# 2015Xover.net
KiCad netlist of a schematic drawn in EAGLE
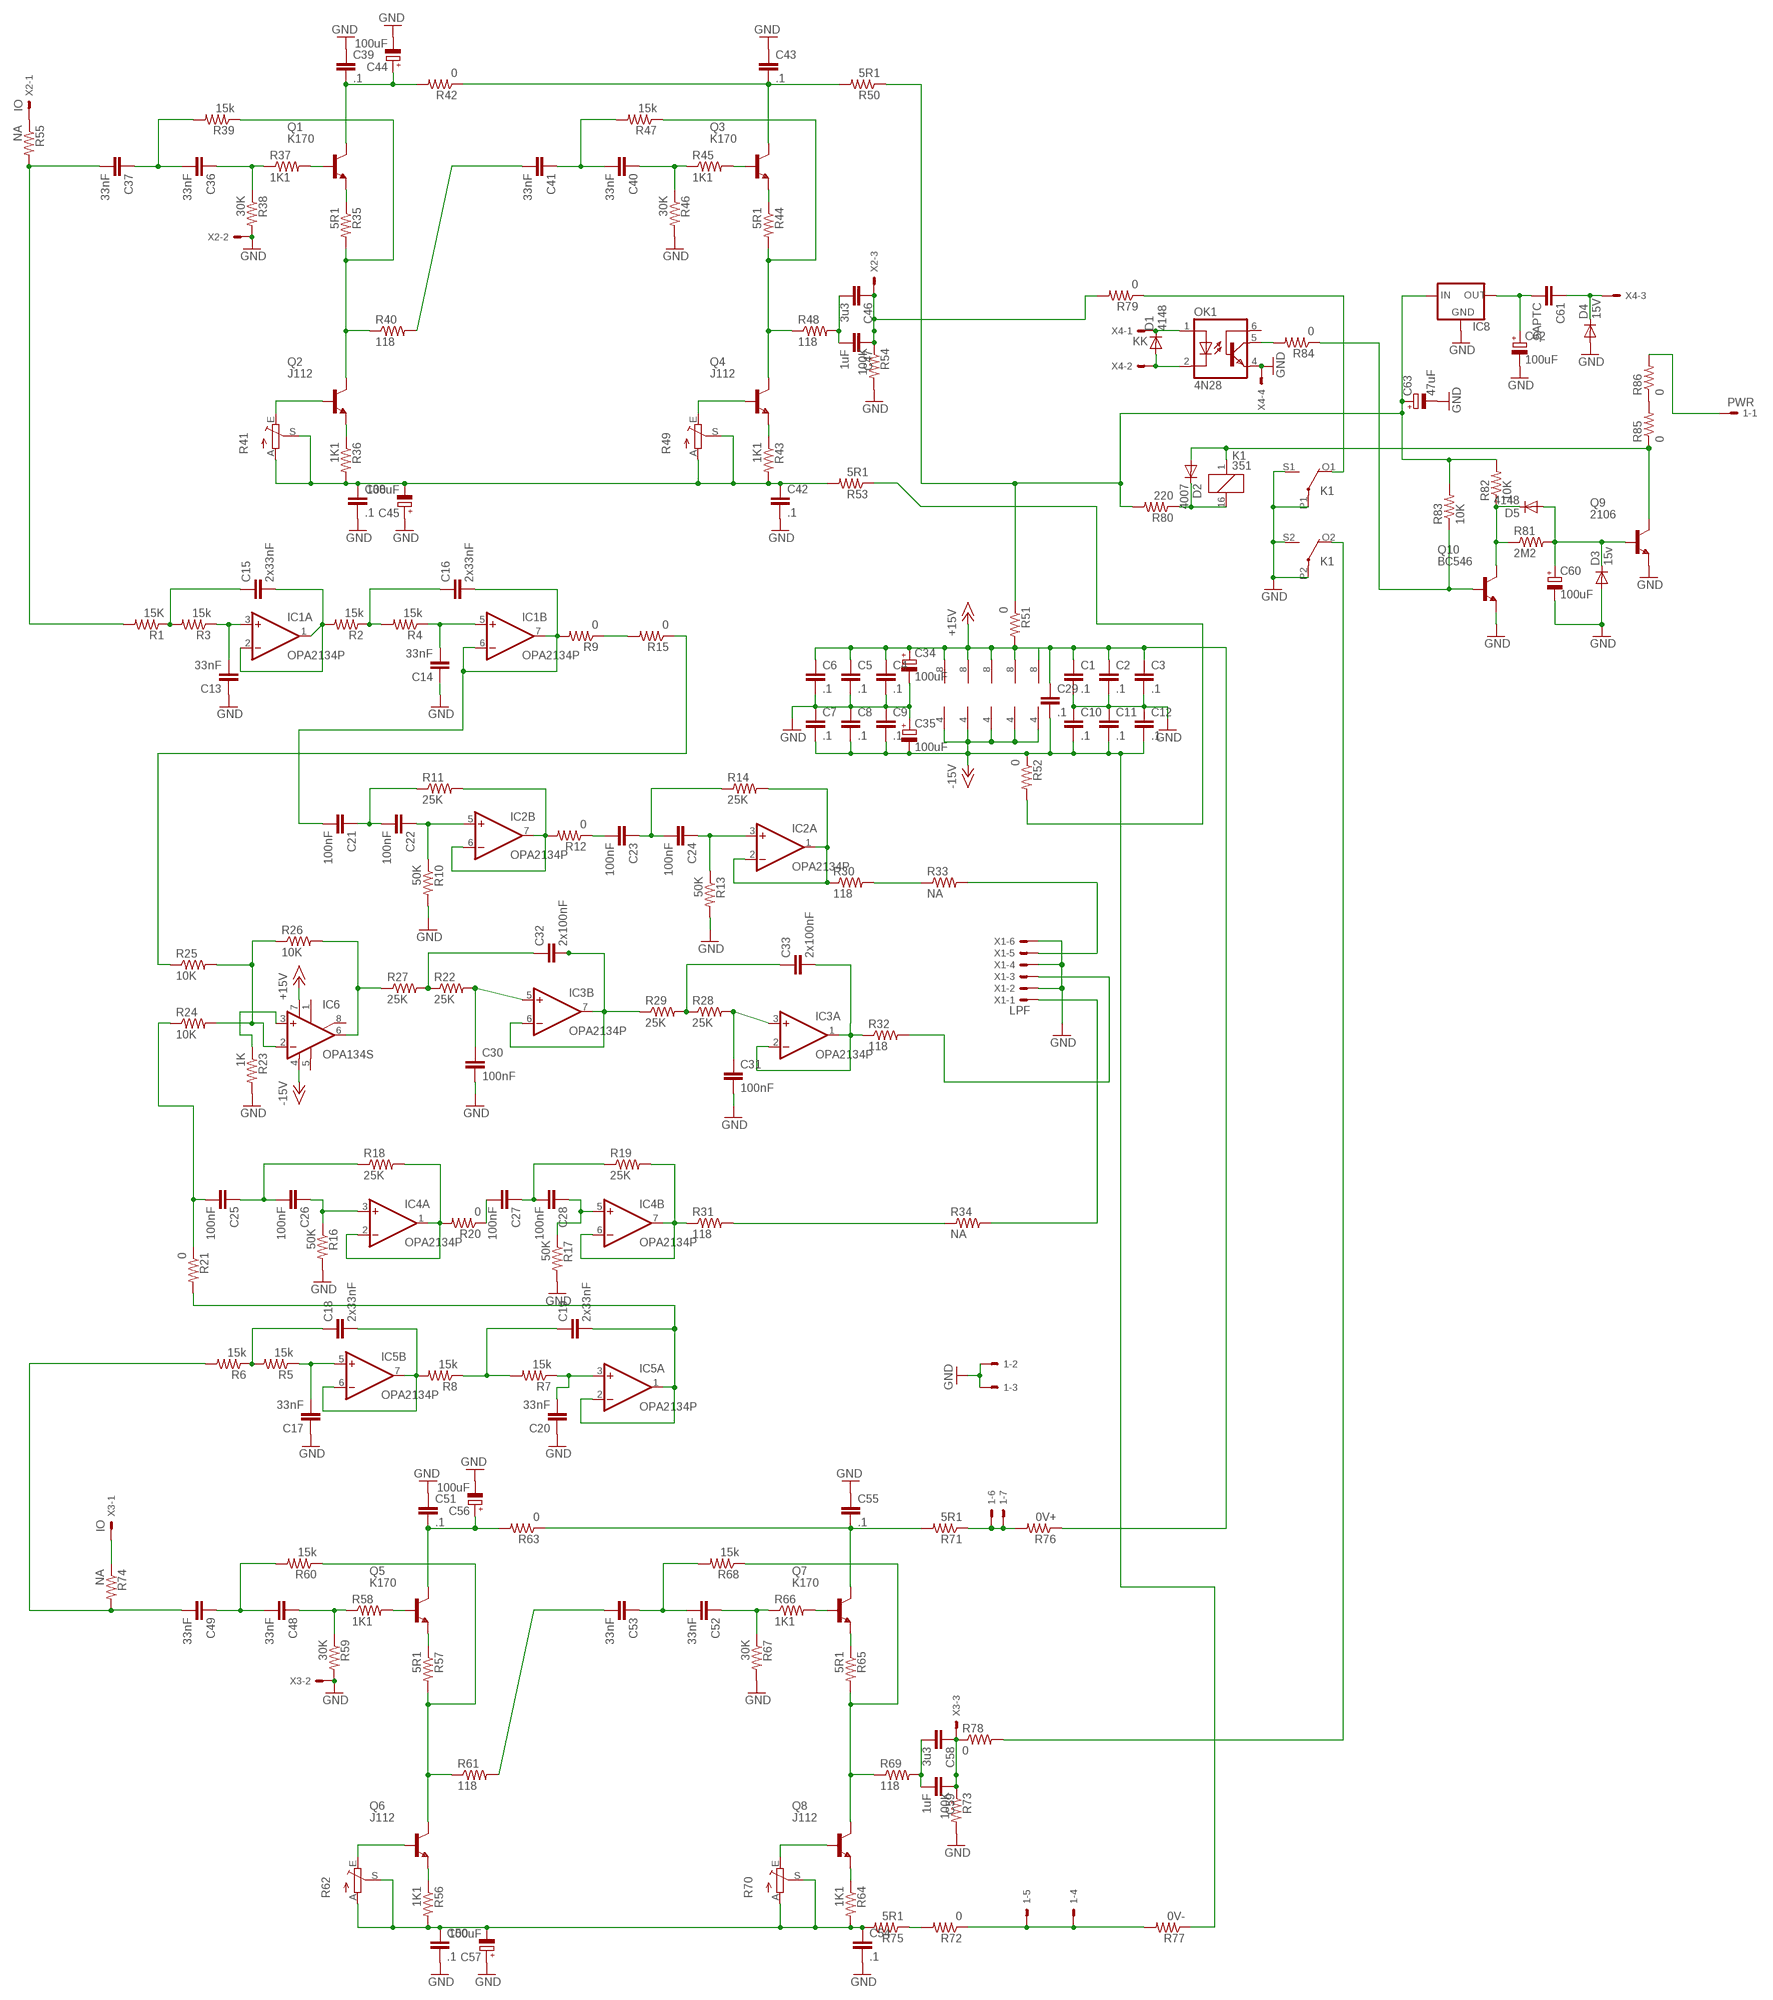
[diagram p0: schematic, sheet 1]

(export (version "E")
  (design (tool "Eeschema 10.0.6"))
  (components
    (comp (ref "1")
      (value "PWR")
      (footprint "eagle-import:22-23-2071")
      (fields (field (name "MF") "MOLEX") (field (name "MPN") "22-23-2071"))
      (libsource (lib "eagle-import") (part "22-23-2071"))
    )
    (comp (ref "C1")
      (value ".1")
      (footprint "eagle-import:C4532")
      (libsource (lib "eagle-import") (part "C-EUC4532"))
    )
    (comp (ref "C2")
      (value ".1")
      (footprint "eagle-import:C4532")
      (libsource (lib "eagle-import") (part "C-EUC4532"))
    )
    (comp (ref "C3")
      (value ".1")
      (footprint "eagle-import:C4532")
      (libsource (lib "eagle-import") (part "C-EUC4532"))
    )
    (comp (ref "C4")
      (value ".1")
      (footprint "eagle-import:C4532")
      (libsource (lib "eagle-import") (part "C-EUC4532"))
    )
    (comp (ref "C5")
      (value ".1")
      (footprint "eagle-import:C4532")
      (libsource (lib "eagle-import") (part "C-EUC4532"))
    )
    (comp (ref "C6")
      (value ".1")
      (footprint "eagle-import:C4532")
      (libsource (lib "eagle-import") (part "C-EUC4532"))
    )
    (comp (ref "C7")
      (value ".1")
      (footprint "eagle-import:C4532")
      (libsource (lib "eagle-import") (part "C-EUC4532"))
    )
    (comp (ref "C8")
      (value ".1")
      (footprint "eagle-import:C4532")
      (libsource (lib "eagle-import") (part "C-EUC4532"))
    )
    (comp (ref "C9")
      (value ".1")
      (footprint "eagle-import:C4532")
      (libsource (lib "eagle-import") (part "C-EUC4532"))
    )
    (comp (ref "C10")
      (value ".1")
      (footprint "eagle-import:C4532")
      (libsource (lib "eagle-import") (part "C-EUC4532"))
    )
    (comp (ref "C11")
      (value ".1")
      (footprint "eagle-import:C4532")
      (libsource (lib "eagle-import") (part "C-EUC4532"))
    )
    (comp (ref "C12")
      (value ".1")
      (footprint "eagle-import:C4532")
      (libsource (lib "eagle-import") (part "C-EUC4532"))
    )
    (comp (ref "C13")
      (value "33nF")
      (footprint "eagle-import:C050-075X075")
      (libsource (lib "eagle-import") (part "C-EU050-075X075"))
    )
    (comp (ref "C14")
      (value "33nF")
      (footprint "eagle-import:C050-075X075")
      (libsource (lib "eagle-import") (part "C-EU050-075X075"))
    )
    (comp (ref "C15")
      (value "2x33nF")
      (footprint "eagle-import:C050-075X075")
      (libsource (lib "eagle-import") (part "C-EU050-075X075"))
    )
    (comp (ref "C16")
      (value "2x33nF")
      (footprint "eagle-import:C050-075X075")
      (libsource (lib "eagle-import") (part "C-EU050-075X075"))
    )
    (comp (ref "C17")
      (value "33nF")
      (footprint "eagle-import:C050-075X075")
      (libsource (lib "eagle-import") (part "C-EU050-075X075"))
    )
    (comp (ref "C18")
      (value "2x33nF")
      (footprint "eagle-import:C050-075X075")
      (libsource (lib "eagle-import") (part "C-EU050-075X075"))
    )
    (comp (ref "C19")
      (value "2x33nF")
      (footprint "eagle-import:C050-075X075")
      (libsource (lib "eagle-import") (part "C-EU050-075X075"))
    )
    (comp (ref "C20")
      (value "33nF")
      (footprint "eagle-import:C050-075X075")
      (libsource (lib "eagle-import") (part "C-EU050-075X075"))
    )
    (comp (ref "C21")
      (value "100nF")
      (footprint "eagle-import:C050-075X075")
      (libsource (lib "eagle-import") (part "C-EU050-075X075"))
    )
    (comp (ref "C22")
      (value "100nF")
      (footprint "eagle-import:C050-075X075")
      (libsource (lib "eagle-import") (part "C-EU050-075X075"))
    )
    (comp (ref "C23")
      (value "100nF")
      (footprint "eagle-import:C050-075X075")
      (libsource (lib "eagle-import") (part "C-EU050-075X075"))
    )
    (comp (ref "C24")
      (value "100nF")
      (footprint "eagle-import:C050-075X075")
      (libsource (lib "eagle-import") (part "C-EU050-075X075"))
    )
    (comp (ref "C25")
      (value "100nF")
      (footprint "eagle-import:C050-075X075")
      (libsource (lib "eagle-import") (part "C-EU050-075X075"))
    )
    (comp (ref "C26")
      (value "100nF")
      (footprint "eagle-import:C050-075X075")
      (libsource (lib "eagle-import") (part "C-EU050-075X075"))
    )
    (comp (ref "C27")
      (value "100nF")
      (footprint "eagle-import:C050-075X075")
      (libsource (lib "eagle-import") (part "C-EU050-075X075"))
    )
    (comp (ref "C28")
      (value "100nF")
      (footprint "eagle-import:C050-075X075")
      (libsource (lib "eagle-import") (part "C-EU050-075X075"))
    )
    (comp (ref "C29")
      (value ".1")
      (footprint "eagle-import:C4532")
      (libsource (lib "eagle-import") (part "C-EUC4532"))
    )
    (comp (ref "C30")
      (value "100nF")
      (footprint "eagle-import:C050-075X075")
      (libsource (lib "eagle-import") (part "C-EU050-075X075"))
    )
    (comp (ref "C31")
      (value "100nF")
      (footprint "eagle-import:C050-075X075")
      (libsource (lib "eagle-import") (part "C-EU050-075X075"))
    )
    (comp (ref "C32")
      (value "2x100nF")
      (footprint "eagle-import:C050-075X075")
      (libsource (lib "eagle-import") (part "C-EU050-075X075"))
    )
    (comp (ref "C33")
      (value "2x100nF")
      (footprint "eagle-import:C050-075X075")
      (libsource (lib "eagle-import") (part "C-EU050-075X075"))
    )
    (comp (ref "C34")
      (value "100uF")
      (footprint "eagle-import:E5-10,5")
      (libsource (lib "eagle-import") (part "CPOL-EUE5-10.5"))
    )
    (comp (ref "C35")
      (value "100uF")
      (footprint "eagle-import:E5-10,5")
      (libsource (lib "eagle-import") (part "CPOL-EUE5-10.5"))
    )
    (comp (ref "C36")
      (value "33nF")
      (footprint "eagle-import:C050-075X075")
      (libsource (lib "eagle-import") (part "C-EU050-075X075"))
    )
    (comp (ref "C37")
      (value "33nF")
      (footprint "eagle-import:C050-075X075")
      (libsource (lib "eagle-import") (part "C-EU050-075X075"))
    )
    (comp (ref "C38")
      (value ".1")
      (footprint "eagle-import:C4532")
      (libsource (lib "eagle-import") (part "C-EUC4532"))
    )
    (comp (ref "C39")
      (value ".1")
      (footprint "eagle-import:C4532")
      (libsource (lib "eagle-import") (part "C-EUC4532"))
    )
    (comp (ref "C40")
      (value "33nF")
      (footprint "eagle-import:C050-075X075")
      (libsource (lib "eagle-import") (part "C-EU050-075X075"))
    )
    (comp (ref "C41")
      (value "33nF")
      (footprint "eagle-import:C050-075X075")
      (libsource (lib "eagle-import") (part "C-EU050-075X075"))
    )
    (comp (ref "C42")
      (value ".1")
      (footprint "eagle-import:C4532")
      (libsource (lib "eagle-import") (part "C-EUC4532"))
    )
    (comp (ref "C43")
      (value ".1")
      (footprint "eagle-import:C4532")
      (libsource (lib "eagle-import") (part "C-EUC4532"))
    )
    (comp (ref "C44")
      (value "100uF")
      (footprint "eagle-import:E5-10,5")
      (libsource (lib "eagle-import") (part "CPOL-EUE5-10.5"))
    )
    (comp (ref "C45")
      (value "100uF")
      (footprint "eagle-import:E5-10,5")
      (libsource (lib "eagle-import") (part "CPOL-EUE5-10.5"))
    )
    (comp (ref "C46")
      (value "3u3")
      (footprint "eagle-import:C275-134X316")
      (libsource (lib "eagle-import") (part "C-EU275-134X316"))
    )
    (comp (ref "C47")
      (value "1uF")
      (footprint "eagle-import:C275-134X316")
      (libsource (lib "eagle-import") (part "C-EU275-134X316"))
    )
    (comp (ref "C48")
      (value "33nF")
      (footprint "eagle-import:C050-075X075")
      (libsource (lib "eagle-import") (part "C-EU050-075X075"))
    )
    (comp (ref "C49")
      (value "33nF")
      (footprint "eagle-import:C050-075X075")
      (libsource (lib "eagle-import") (part "C-EU050-075X075"))
    )
    (comp (ref "C50")
      (value ".1")
      (footprint "eagle-import:C4532")
      (libsource (lib "eagle-import") (part "C-EUC4532"))
    )
    (comp (ref "C51")
      (value ".1")
      (footprint "eagle-import:C4532")
      (libsource (lib "eagle-import") (part "C-EUC4532"))
    )
    (comp (ref "C52")
      (value "33nF")
      (footprint "eagle-import:C050-075X075")
      (libsource (lib "eagle-import") (part "C-EU050-075X075"))
    )
    (comp (ref "C53")
      (value "33nF")
      (footprint "eagle-import:C050-075X075")
      (libsource (lib "eagle-import") (part "C-EU050-075X075"))
    )
    (comp (ref "C54")
      (value ".1")
      (footprint "eagle-import:C4532")
      (libsource (lib "eagle-import") (part "C-EUC4532"))
    )
    (comp (ref "C55")
      (value ".1")
      (footprint "eagle-import:C4532")
      (libsource (lib "eagle-import") (part "C-EUC4532"))
    )
    (comp (ref "C56")
      (value "100uF")
      (footprint "eagle-import:E5-10,5")
      (libsource (lib "eagle-import") (part "CPOL-EUE5-10.5"))
    )
    (comp (ref "C57")
      (value "100uF")
      (footprint "eagle-import:E5-10,5")
      (libsource (lib "eagle-import") (part "CPOL-EUE5-10.5"))
    )
    (comp (ref "C58")
      (value "3u3")
      (footprint "eagle-import:C275-134X316")
      (libsource (lib "eagle-import") (part "C-EU275-134X316"))
    )
    (comp (ref "C59")
      (value "1uF")
      (footprint "eagle-import:C275-134X316")
      (libsource (lib "eagle-import") (part "C-EU275-134X316"))
    )
    (comp (ref "C60")
      (value "100uF")
      (footprint "eagle-import:E5-10,5")
      (libsource (lib "eagle-import") (part "CPOL-EUE5-10.5"))
    )
    (comp (ref "C61")
      (value ".5APTC")
      (footprint "eagle-import:C050-075X075")
      (libsource (lib "eagle-import") (part "C-EU050-075X075"))
    )
    (comp (ref "C62")
      (value "100uF")
      (footprint "eagle-import:E5-10,5")
      (libsource (lib "eagle-import") (part "CPOL-EUE5-10.5"))
    )
    (comp (ref "C63")
      (value "47uF")
      (footprint "eagle-import:E5-10,5")
      (libsource (lib "eagle-import") (part "CPOL-EUE5-10.5"))
    )
    (comp (ref "D1")
      (value "4148")
      (footprint "eagle-import:DO35-7")
      (libsource (lib "eagle-import") (part "1N4148DO35-7"))
    )
    (comp (ref "D2")
      (value "4007")
      (footprint "eagle-import:DO35-7")
      (libsource (lib "eagle-import") (part "1N4148DO35-7"))
    )
    (comp (ref "D3")
      (value "15v")
      (footprint "eagle-import:DO35-7")
      (libsource (lib "eagle-import") (part "1N4148DO35-7"))
    )
    (comp (ref "D4")
      (value "15V")
      (footprint "eagle-import:DO35-7")
      (libsource (lib "eagle-import") (part "1N4148DO35-7"))
    )
    (comp (ref "D5")
      (value "4148")
      (footprint "eagle-import:DO35-7")
      (libsource (lib "eagle-import") (part "1N4148DO35-7"))
    )
    (comp (ref "IC1")
      (value "OPA2134P")
      (footprint "eagle-import:DIL08")
      (libsource (lib "eagle-import") (part "OPA2134P"))
    )
    (comp (ref "IC2")
      (value "OPA2134P")
      (footprint "eagle-import:DIL08")
      (libsource (lib "eagle-import") (part "OPA2134P"))
    )
    (comp (ref "IC3")
      (value "OPA2134P")
      (footprint "eagle-import:DIL08")
      (libsource (lib "eagle-import") (part "OPA2134P"))
    )
    (comp (ref "IC4")
      (value "OPA2134P")
      (footprint "eagle-import:DIL08")
      (libsource (lib "eagle-import") (part "OPA2134P"))
    )
    (comp (ref "IC5")
      (value "OPA2134P")
      (footprint "eagle-import:DIL08")
      (libsource (lib "eagle-import") (part "OPA2134P"))
    )
    (comp (ref "IC6")
      (value "OPA134S")
      (footprint "eagle-import:DIL08")
      (libsource (lib "eagle-import") (part "OPA134P"))
    )
    (comp (ref "IC8")
      (value "78XXS")
      (footprint "eagle-import:78XXS")
      (libsource (lib "eagle-import") (part "78XXS"))
    )
    (comp (ref "K1")
      (value "351")
      (footprint "eagle-import:351")
      (libsource (lib "eagle-import") (part "351"))
    )
    (comp (ref "OK1")
      (value "4N28")
      (footprint "eagle-import:DIL06")
      (fields (field (name "MF") "FAIRCHILD SEMICONDUCTOR") (field (name "MPN") "4N35"))
      (libsource (lib "eagle-import") (part "4N35"))
    )
    (comp (ref "Q1")
      (value "K170")
      (footprint "eagle-import:TO92-EBC")
      (libsource (lib "eagle-import") (part "BC546A"))
    )
    (comp (ref "Q2")
      (value "J112")
      (footprint "eagle-import:TO92-EBC")
      (libsource (lib "eagle-import") (part "BC546A"))
    )
    (comp (ref "Q3")
      (value "K170")
      (footprint "eagle-import:TO92-EBC")
      (libsource (lib "eagle-import") (part "BC546A"))
    )
    (comp (ref "Q4")
      (value "J112")
      (footprint "eagle-import:TO92-EBC")
      (libsource (lib "eagle-import") (part "BC546A"))
    )
    (comp (ref "Q5")
      (value "K170")
      (footprint "eagle-import:TO92-EBC")
      (libsource (lib "eagle-import") (part "BC546A"))
    )
    (comp (ref "Q6")
      (value "J112")
      (footprint "eagle-import:TO92-EBC")
      (libsource (lib "eagle-import") (part "BC546A"))
    )
    (comp (ref "Q7")
      (value "K170")
      (footprint "eagle-import:TO92-EBC")
      (libsource (lib "eagle-import") (part "BC546A"))
    )
    (comp (ref "Q8")
      (value "J112")
      (footprint "eagle-import:TO92-EBC")
      (libsource (lib "eagle-import") (part "BC546A"))
    )
    (comp (ref "Q9")
      (value "2106")
      (footprint "eagle-import:TO92-EBC")
      (libsource (lib "eagle-import") (part "BC546A"))
    )
    (comp (ref "Q10")
      (value "BC546")
      (footprint "eagle-import:TO92-EBC")
      (libsource (lib "eagle-import") (part "BC546A"))
    )
    (comp (ref "R1")
      (value "15K")
      (footprint "eagle-import:0309_10")
      (libsource (lib "eagle-import") (part "R-US_0309/10"))
    )
    (comp (ref "R2")
      (value "15k")
      (footprint "eagle-import:0309_12")
      (libsource (lib "eagle-import") (part "R-US_0309/12"))
    )
    (comp (ref "R3")
      (value "15k")
      (footprint "eagle-import:0309_10")
      (libsource (lib "eagle-import") (part "R-US_0309/10"))
    )
    (comp (ref "R4")
      (value "15k")
      (footprint "eagle-import:0309_12")
      (libsource (lib "eagle-import") (part "R-US_0309/12"))
    )
    (comp (ref "R5")
      (value "15k")
      (footprint "eagle-import:0309_10")
      (libsource (lib "eagle-import") (part "R-US_0309/10"))
    )
    (comp (ref "R6")
      (value "15k")
      (footprint "eagle-import:0309_10")
      (libsource (lib "eagle-import") (part "R-US_0309/10"))
    )
    (comp (ref "R7")
      (value "15k")
      (footprint "eagle-import:0309_10")
      (libsource (lib "eagle-import") (part "R-US_0309/10"))
    )
    (comp (ref "R8")
      (value "15k")
      (footprint "eagle-import:0309_12")
      (libsource (lib "eagle-import") (part "R-US_0309/12"))
    )
    (comp (ref "R9")
      (value "0")
      (footprint "eagle-import:0309_12")
      (libsource (lib "eagle-import") (part "R-US_0309/12"))
    )
    (comp (ref "R10")
      (value "50K")
      (footprint "eagle-import:0309_10")
      (libsource (lib "eagle-import") (part "R-US_0309/10"))
    )
    (comp (ref "R11")
      (value "25K")
      (footprint "eagle-import:0309_10")
      (libsource (lib "eagle-import") (part "R-US_0309/10"))
    )
    (comp (ref "R12")
      (value "0")
      (footprint "eagle-import:0309_12")
      (libsource (lib "eagle-import") (part "R-US_0309/12"))
    )
    (comp (ref "R13")
      (value "50K")
      (footprint "eagle-import:0309_12")
      (libsource (lib "eagle-import") (part "R-US_0309/12"))
    )
    (comp (ref "R14")
      (value "25K")
      (footprint "eagle-import:0309_10")
      (libsource (lib "eagle-import") (part "R-US_0309/10"))
    )
    (comp (ref "R15")
      (value "0")
      (footprint "eagle-import:0309_12")
      (libsource (lib "eagle-import") (part "R-US_0309/12"))
    )
    (comp (ref "R16")
      (value "50K")
      (footprint "eagle-import:0309_12")
      (libsource (lib "eagle-import") (part "R-US_0309/12"))
    )
    (comp (ref "R17")
      (value "50K")
      (footprint "eagle-import:0309_10")
      (libsource (lib "eagle-import") (part "R-US_0309/10"))
    )
    (comp (ref "R18")
      (value "25K")
      (footprint "eagle-import:0309_10")
      (libsource (lib "eagle-import") (part "R-US_0309/10"))
    )
    (comp (ref "R19")
      (value "25K")
      (footprint "eagle-import:0309_10")
      (libsource (lib "eagle-import") (part "R-US_0309/10"))
    )
    (comp (ref "R20")
      (value "0")
      (footprint "eagle-import:0309_12")
      (libsource (lib "eagle-import") (part "R-US_0309/12"))
    )
    (comp (ref "R21")
      (value "0")
      (footprint "eagle-import:0309_10")
      (libsource (lib "eagle-import") (part "R-US_0309/10"))
    )
    (comp (ref "R22")
      (value "25K")
      (footprint "eagle-import:0309_10")
      (libsource (lib "eagle-import") (part "R-US_0309/10"))
    )
    (comp (ref "R23")
      (value "1K")
      (footprint "eagle-import:0309_10")
      (libsource (lib "eagle-import") (part "R-US_0309/10"))
    )
    (comp (ref "R24")
      (value "10K")
      (footprint "eagle-import:0309_10")
      (libsource (lib "eagle-import") (part "R-US_0309/10"))
    )
    (comp (ref "R25")
      (value "10K")
      (footprint "eagle-import:0309_12")
      (libsource (lib "eagle-import") (part "R-US_0309/12"))
    )
    (comp (ref "R26")
      (value "10K")
      (footprint "eagle-import:0309_12")
      (libsource (lib "eagle-import") (part "R-US_0309/12"))
    )
    (comp (ref "R27")
      (value "25K")
      (footprint "eagle-import:0309_10")
      (libsource (lib "eagle-import") (part "R-US_0309/10"))
    )
    (comp (ref "R28")
      (value "25K")
      (footprint "eagle-import:0309_10")
      (libsource (lib "eagle-import") (part "R-US_0309/10"))
    )
    (comp (ref "R29")
      (value "25K")
      (footprint "eagle-import:0309_12")
      (libsource (lib "eagle-import") (part "R-US_0309/12"))
    )
    (comp (ref "R30")
      (value "118")
      (footprint "eagle-import:0309_10")
      (libsource (lib "eagle-import") (part "R-US_0309/10"))
    )
    (comp (ref "R31")
      (value "118")
      (footprint "eagle-import:0309_12")
      (libsource (lib "eagle-import") (part "R-US_0309/12"))
    )
    (comp (ref "R32")
      (value "118")
      (footprint "eagle-import:0309_10")
      (libsource (lib "eagle-import") (part "R-US_0309/10"))
    )
    (comp (ref "R33")
      (value "NA")
      (footprint "eagle-import:0309_10")
      (libsource (lib "eagle-import") (part "R-US_0309/10"))
    )
    (comp (ref "R34")
      (value "NA")
      (footprint "eagle-import:0309_10")
      (libsource (lib "eagle-import") (part "R-US_0309/10"))
    )
    (comp (ref "R35")
      (value "5R1")
      (footprint "eagle-import:0309_10")
      (libsource (lib "eagle-import") (part "R-US_0309/10"))
    )
    (comp (ref "R36")
      (value "1K1")
      (footprint "eagle-import:R1210")
      (libsource (lib "eagle-import") (part "R-US_R1210"))
    )
    (comp (ref "R37")
      (value "1K1")
      (footprint "eagle-import:R1210")
      (libsource (lib "eagle-import") (part "R-US_R1210"))
    )
    (comp (ref "R38")
      (value "30K")
      (footprint "eagle-import:0309_10")
      (libsource (lib "eagle-import") (part "R-US_0309/10"))
    )
    (comp (ref "R39")
      (value "15k")
      (footprint "eagle-import:0309_10")
      (libsource (lib "eagle-import") (part "R-US_0309/10"))
    )
    (comp (ref "R40")
      (value "118")
      (footprint "eagle-import:0309_10")
      (libsource (lib "eagle-import") (part "R-US_0309/10"))
    )
    (comp (ref "R41")
      (value "TRIM_EU-RJ9W")
      (footprint "eagle-import:RJ9W")
      (libsource (lib "eagle-import") (part "TRIM_EU-RJ9W"))
    )
    (comp (ref "R42")
      (value "0")
      (footprint "eagle-import:0309_10")
      (libsource (lib "eagle-import") (part "R-US_0309/10"))
    )
    (comp (ref "R43")
      (value "1K1")
      (footprint "eagle-import:R1210")
      (libsource (lib "eagle-import") (part "R-US_R1210"))
    )
    (comp (ref "R44")
      (value "5R1")
      (footprint "eagle-import:0309_10")
      (libsource (lib "eagle-import") (part "R-US_0309/10"))
    )
    (comp (ref "R45")
      (value "1K1")
      (footprint "eagle-import:R1210")
      (libsource (lib "eagle-import") (part "R-US_R1210"))
    )
    (comp (ref "R46")
      (value "30K")
      (footprint "eagle-import:0309_10")
      (libsource (lib "eagle-import") (part "R-US_0309/10"))
    )
    (comp (ref "R47")
      (value "15k")
      (footprint "eagle-import:0309_10")
      (libsource (lib "eagle-import") (part "R-US_0309/10"))
    )
    (comp (ref "R48")
      (value "118")
      (footprint "eagle-import:0309_10")
      (libsource (lib "eagle-import") (part "R-US_0309/10"))
    )
    (comp (ref "R49")
      (value "TRIM_EU-RJ9W")
      (footprint "eagle-import:RJ9W")
      (libsource (lib "eagle-import") (part "TRIM_EU-RJ9W"))
    )
    (comp (ref "R50")
      (value "5R1")
      (footprint "eagle-import:0309_10")
      (libsource (lib "eagle-import") (part "R-US_0309/10"))
    )
    (comp (ref "R51")
      (value "0")
      (footprint "eagle-import:0309_10")
      (libsource (lib "eagle-import") (part "R-US_0309/10"))
    )
    (comp (ref "R52")
      (value "0")
      (footprint "eagle-import:0309_10")
      (libsource (lib "eagle-import") (part "R-US_0309/10"))
    )
    (comp (ref "R53")
      (value "5R1")
      (footprint "eagle-import:0309_10")
      (libsource (lib "eagle-import") (part "R-US_0309/10"))
    )
    (comp (ref "R54")
      (value "100K")
      (footprint "eagle-import:0309_10")
      (libsource (lib "eagle-import") (part "R-US_0309/10"))
    )
    (comp (ref "R55")
      (value "NA")
      (footprint "eagle-import:0309_12")
      (libsource (lib "eagle-import") (part "R-US_0309/12"))
    )
    (comp (ref "R56")
      (value "1K1")
      (footprint "eagle-import:R1210")
      (libsource (lib "eagle-import") (part "R-US_R1210"))
    )
    (comp (ref "R57")
      (value "5R1")
      (footprint "eagle-import:0309_10")
      (libsource (lib "eagle-import") (part "R-US_0309/10"))
    )
    (comp (ref "R58")
      (value "1K1")
      (footprint "eagle-import:R1210")
      (libsource (lib "eagle-import") (part "R-US_R1210"))
    )
    (comp (ref "R59")
      (value "30K")
      (footprint "eagle-import:0309_10")
      (libsource (lib "eagle-import") (part "R-US_0309/10"))
    )
    (comp (ref "R60")
      (value "15k")
      (footprint "eagle-import:0309_10")
      (libsource (lib "eagle-import") (part "R-US_0309/10"))
    )
    (comp (ref "R61")
      (value "118")
      (footprint "eagle-import:0309_10")
      (libsource (lib "eagle-import") (part "R-US_0309/10"))
    )
    (comp (ref "R62")
      (value "TRIM_EU-RJ9W")
      (footprint "eagle-import:RJ9W")
      (libsource (lib "eagle-import") (part "TRIM_EU-RJ9W"))
    )
    (comp (ref "R63")
      (value "0")
      (footprint "eagle-import:0309_10")
      (libsource (lib "eagle-import") (part "R-US_0309/10"))
    )
    (comp (ref "R64")
      (value "1K1")
      (footprint "eagle-import:R1210")
      (libsource (lib "eagle-import") (part "R-US_R1210"))
    )
    (comp (ref "R65")
      (value "5R1")
      (footprint "eagle-import:0309_10")
      (libsource (lib "eagle-import") (part "R-US_0309/10"))
    )
    (comp (ref "R66")
      (value "1K1")
      (footprint "eagle-import:R1210")
      (libsource (lib "eagle-import") (part "R-US_R1210"))
    )
    (comp (ref "R67")
      (value "30K")
      (footprint "eagle-import:0309_10")
      (libsource (lib "eagle-import") (part "R-US_0309/10"))
    )
    (comp (ref "R68")
      (value "15k")
      (footprint "eagle-import:0309_10")
      (libsource (lib "eagle-import") (part "R-US_0309/10"))
    )
    (comp (ref "R69")
      (value "118")
      (footprint "eagle-import:0309_10")
      (libsource (lib "eagle-import") (part "R-US_0309/10"))
    )
    (comp (ref "R70")
      (value "TRIM_EU-RJ9W")
      (footprint "eagle-import:RJ9W")
      (libsource (lib "eagle-import") (part "TRIM_EU-RJ9W"))
    )
    (comp (ref "R71")
      (value "5R1")
      (footprint "eagle-import:0309_10")
      (libsource (lib "eagle-import") (part "R-US_0309/10"))
    )
    (comp (ref "R72")
      (value "0")
      (footprint "eagle-import:0309_12")
      (libsource (lib "eagle-import") (part "R-US_0309/12"))
    )
    (comp (ref "R73")
      (value "100K")
      (footprint "eagle-import:0309_10")
      (libsource (lib "eagle-import") (part "R-US_0309/10"))
    )
    (comp (ref "R74")
      (value "NA")
      (footprint "eagle-import:0309_12")
      (libsource (lib "eagle-import") (part "R-US_0309/12"))
    )
    (comp (ref "R75")
      (value "5R1")
      (footprint "eagle-import:0309_10")
      (libsource (lib "eagle-import") (part "R-US_0309/10"))
    )
    (comp (ref "R76")
      (value "0V+")
      (footprint "eagle-import:0309_10")
      (libsource (lib "eagle-import") (part "R-US_0309/10"))
    )
    (comp (ref "R77")
      (value "0V-")
      (footprint "eagle-import:0309_12")
      (libsource (lib "eagle-import") (part "R-US_0309/12"))
    )
    (comp (ref "R78")
      (value "0")
      (footprint "eagle-import:0309_12")
      (libsource (lib "eagle-import") (part "R-US_0309/12"))
    )
    (comp (ref "R79")
      (value "0")
      (footprint "eagle-import:0309_10")
      (libsource (lib "eagle-import") (part "R-US_0309/10"))
    )
    (comp (ref "R80")
      (value "220")
      (footprint "eagle-import:0309_10")
      (libsource (lib "eagle-import") (part "R-US_0309/10"))
    )
    (comp (ref "R81")
      (value "2M2")
      (footprint "eagle-import:0207_10")
      (libsource (lib "eagle-import") (part "R-US_0207/10"))
    )
    (comp (ref "R82")
      (value "10K")
      (footprint "eagle-import:0207_10")
      (libsource (lib "eagle-import") (part "R-US_0207/10"))
    )
    (comp (ref "R83")
      (value "10K")
      (footprint "eagle-import:0207_10")
      (libsource (lib "eagle-import") (part "R-US_0207/10"))
    )
    (comp (ref "R84")
      (value "0")
      (footprint "eagle-import:0309_10")
      (libsource (lib "eagle-import") (part "R-US_0309/10"))
    )
    (comp (ref "R85")
      (value "0")
      (footprint "eagle-import:0207_12")
      (libsource (lib "eagle-import") (part "R-US_0207/12"))
    )
    (comp (ref "R86")
      (value "0")
      (footprint "eagle-import:0207_10")
      (libsource (lib "eagle-import") (part "R-US_0207/10"))
    )
    (comp (ref "X1")
      (value "LPF")
      (footprint "eagle-import:22-23-2061")
      (fields (field (name "MF") "MOLEX") (field (name "MPN") "22-23-2061"))
      (libsource (lib "eagle-import") (part "22-23-2061"))
    )
    (comp (ref "X2")
      (value "IO")
      (footprint "eagle-import:22-23-2031")
      (fields (field (name "MF") "MOLEX") (field (name "MPN") "22-23-2031"))
      (libsource (lib "eagle-import") (part "22-23-2031"))
    )
    (comp (ref "X3")
      (value "IO")
      (footprint "eagle-import:22-23-2031")
      (fields (field (name "MF") "MOLEX") (field (name "MPN") "22-23-2031"))
      (libsource (lib "eagle-import") (part "22-23-2031"))
    )
    (comp (ref "X4")
      (value "KK")
      (footprint "eagle-import:22-23-2041")
      (fields (field (name "MF") "MOLEX") (field (name "MPN") "22-23-2041"))
      (libsource (lib "eagle-import") (part "22-23-2041"))
    )
  )
  (nets
    (net (code "1") (name "+15V") (class "Default")
      (node (ref "C1") (pin "1") (pinfunction "1_1") (pintype "passive"))
      (node (ref "C2") (pin "1") (pinfunction "1_1") (pintype "passive"))
      (node (ref "C29") (pin "1") (pinfunction "1_1") (pintype "passive"))
      (node (ref "C3") (pin "1") (pinfunction "1_1") (pintype "passive"))
      (node (ref "C34") (pin "+") (pinfunction "+_+") (pintype "passive"))
      (node (ref "C4") (pin "1") (pinfunction "1_1") (pintype "passive"))
      (node (ref "C5") (pin "1") (pinfunction "1_1") (pintype "passive"))
      (node (ref "C6") (pin "1") (pinfunction "1_1") (pintype "passive"))
      (node (ref "IC1") (pin "8") (pinfunction "V+_8") (pintype "power_in"))
      (node (ref "IC2") (pin "8") (pinfunction "V+_8") (pintype "power_in"))
      (node (ref "IC3") (pin "8") (pinfunction "V+_8") (pintype "power_in"))
      (node (ref "IC4") (pin "8") (pinfunction "V+_8") (pintype "power_in"))
      (node (ref "IC5") (pin "8") (pinfunction "V+_8") (pintype "power_in"))
      (node (ref "IC6") (pin "7") (pinfunction "V+_7") (pintype "power_in"))
      (node (ref "R51") (pin "2") (pinfunction "2_2") (pintype "passive"))
      (node (ref "R76") (pin "1") (pinfunction "1_1") (pintype "passive"))
    )
    (net (code "2") (name "-15V") (class "Default")
      (node (ref "C10") (pin "2") (pinfunction "2_2") (pintype "passive"))
      (node (ref "C11") (pin "2") (pinfunction "2_2") (pintype "passive"))
      (node (ref "C12") (pin "2") (pinfunction "2_2") (pintype "passive"))
      (node (ref "C29") (pin "2") (pinfunction "2_2") (pintype "passive"))
      (node (ref "C35") (pin "-") (pinfunction "-_-") (pintype "passive"))
      (node (ref "C7") (pin "2") (pinfunction "2_2") (pintype "passive"))
      (node (ref "C8") (pin "2") (pinfunction "2_2") (pintype "passive"))
      (node (ref "C9") (pin "2") (pinfunction "2_2") (pintype "passive"))
      (node (ref "IC1") (pin "4") (pinfunction "V-_4") (pintype "power_in"))
      (node (ref "IC2") (pin "4") (pinfunction "V-_4") (pintype "power_in"))
      (node (ref "IC3") (pin "4") (pinfunction "V-_4") (pintype "power_in"))
      (node (ref "IC4") (pin "4") (pinfunction "V-_4") (pintype "power_in"))
      (node (ref "IC5") (pin "4") (pinfunction "V-_4") (pintype "power_in"))
      (node (ref "IC6") (pin "4") (pinfunction "V-_4") (pintype "power_in"))
      (node (ref "R52") (pin "1") (pinfunction "1_1") (pintype "passive"))
      (node (ref "R77") (pin "1") (pinfunction "1_1") (pintype "passive"))
    )
    (net (code "3") (name "GND") (class "Default")
      (node (ref "1") (pin "2") (pinfunction "S_2") (pintype "passive"))
      (node (ref "1") (pin "3") (pinfunction "S_3") (pintype "passive"))
      (node (ref "C1") (pin "2") (pinfunction "2_2") (pintype "passive"))
      (node (ref "C10") (pin "1") (pinfunction "1_1") (pintype "passive"))
      (node (ref "C11") (pin "1") (pinfunction "1_1") (pintype "passive"))
      (node (ref "C12") (pin "1") (pinfunction "1_1") (pintype "passive"))
      (node (ref "C13") (pin "1") (pinfunction "1_1") (pintype "passive"))
      (node (ref "C14") (pin "1") (pinfunction "1_1") (pintype "passive"))
      (node (ref "C17") (pin "1") (pinfunction "1_1") (pintype "passive"))
      (node (ref "C2") (pin "2") (pinfunction "2_2") (pintype "passive"))
      (node (ref "C20") (pin "1") (pinfunction "1_1") (pintype "passive"))
      (node (ref "C3") (pin "2") (pinfunction "2_2") (pintype "passive"))
      (node (ref "C30") (pin "2") (pinfunction "2_2") (pintype "passive"))
      (node (ref "C31") (pin "2") (pinfunction "2_2") (pintype "passive"))
      (node (ref "C34") (pin "-") (pinfunction "-_-") (pintype "passive"))
      (node (ref "C35") (pin "+") (pinfunction "+_+") (pintype "passive"))
      (node (ref "C38") (pin "2") (pinfunction "2_2") (pintype "passive"))
      (node (ref "C39") (pin "1") (pinfunction "1_1") (pintype "passive"))
      (node (ref "C4") (pin "2") (pinfunction "2_2") (pintype "passive"))
      (node (ref "C42") (pin "2") (pinfunction "2_2") (pintype "passive"))
      (node (ref "C43") (pin "1") (pinfunction "1_1") (pintype "passive"))
      (node (ref "C44") (pin "-") (pinfunction "-_-") (pintype "passive"))
      (node (ref "C45") (pin "+") (pinfunction "+_+") (pintype "passive"))
      (node (ref "C5") (pin "2") (pinfunction "2_2") (pintype "passive"))
      (node (ref "C50") (pin "2") (pinfunction "2_2") (pintype "passive"))
      (node (ref "C51") (pin "1") (pinfunction "1_1") (pintype "passive"))
      (node (ref "C54") (pin "2") (pinfunction "2_2") (pintype "passive"))
      (node (ref "C55") (pin "1") (pinfunction "1_1") (pintype "passive"))
      (node (ref "C56") (pin "-") (pinfunction "-_-") (pintype "passive"))
      (node (ref "C57") (pin "+") (pinfunction "+_+") (pintype "passive"))
      (node (ref "C6") (pin "2") (pinfunction "2_2") (pintype "passive"))
      (node (ref "C60") (pin "-") (pinfunction "-_-") (pintype "passive"))
      (node (ref "C62") (pin "-") (pinfunction "-_-") (pintype "passive"))
      (node (ref "C63") (pin "-") (pinfunction "-_-") (pintype "passive"))
      (node (ref "C7") (pin "1") (pinfunction "1_1") (pintype "passive"))
      (node (ref "C8") (pin "1") (pinfunction "1_1") (pintype "passive"))
      (node (ref "C9") (pin "1") (pinfunction "1_1") (pintype "passive"))
      (node (ref "D3") (pin "A") (pinfunction "A_A") (pintype "passive"))
      (node (ref "D4") (pin "A") (pinfunction "A_A") (pintype "passive"))
      (node (ref "IC8") (pin "GND") (pinfunction "GND_GND") (pintype "input"))
      (node (ref "K1") (pin "P1") (pinfunction "P_P1") (pintype "passive"))
      (node (ref "K1") (pin "P2") (pinfunction "P_P2") (pintype "passive"))
      (node (ref "K1") (pin "S1") (pinfunction "S_S1") (pintype "passive"))
      (node (ref "K1") (pin "S2") (pinfunction "S_S2") (pintype "passive"))
      (node (ref "OK1") (pin "4") (pinfunction "EMI_4") (pintype "passive"))
      (node (ref "Q10") (pin "E") (pinfunction "E_E") (pintype "passive"))
      (node (ref "Q9") (pin "E") (pinfunction "E_E") (pintype "passive"))
      (node (ref "R10") (pin "2") (pinfunction "2_2") (pintype "passive"))
      (node (ref "R13") (pin "2") (pinfunction "2_2") (pintype "passive"))
      (node (ref "R16") (pin "2") (pinfunction "2_2") (pintype "passive"))
      (node (ref "R17") (pin "2") (pinfunction "2_2") (pintype "passive"))
      (node (ref "R23") (pin "2") (pinfunction "2_2") (pintype "passive"))
      (node (ref "R38") (pin "2") (pinfunction "2_2") (pintype "passive"))
      (node (ref "R46") (pin "2") (pinfunction "2_2") (pintype "passive"))
      (node (ref "R54") (pin "2") (pinfunction "2_2") (pintype "passive"))
      (node (ref "R59") (pin "2") (pinfunction "2_2") (pintype "passive"))
      (node (ref "R67") (pin "2") (pinfunction "2_2") (pintype "passive"))
      (node (ref "R73") (pin "2") (pinfunction "2_2") (pintype "passive"))
      (node (ref "X1") (pin "2") (pinfunction "S_2") (pintype "passive"))
      (node (ref "X1") (pin "4") (pinfunction "S_4") (pintype "passive"))
      (node (ref "X1") (pin "6") (pinfunction "S_6") (pintype "passive"))
      (node (ref "X2") (pin "2") (pinfunction "S_2") (pintype "passive"))
      (node (ref "X3") (pin "2") (pinfunction "S_2") (pintype "passive"))
      (node (ref "X4") (pin "4") (pinfunction "S_4") (pintype "passive"))
    )
    (net (code "4") (name "Net-(1A-S)") (class "Default")
      (node (ref "1") (pin "1") (pinfunction "S_1") (pintype "passive"))
      (node (ref "R86") (pin "2") (pinfunction "2_2") (pintype "passive"))
    )
    (net (code "5") (name "Net-(1D-S)") (class "Default")
      (node (ref "1") (pin "4") (pinfunction "S_4") (pintype "passive"))
      (node (ref "1") (pin "5") (pinfunction "S_5") (pintype "passive"))
      (node (ref "R72") (pin "1") (pinfunction "1_1") (pintype "passive"))
      (node (ref "R77") (pin "2") (pinfunction "2_2") (pintype "passive"))
    )
    (net (code "6") (name "Net-(1F-S)") (class "Default")
      (node (ref "1") (pin "6") (pinfunction "S_6") (pintype "passive"))
      (node (ref "1") (pin "7") (pinfunction "S_7") (pintype "passive"))
      (node (ref "R71") (pin "1") (pinfunction "1_1") (pintype "passive"))
      (node (ref "R76") (pin "2") (pinfunction "2_2") (pintype "passive"))
    )
    (net (code "7") (name "Net-(C15-Pad1)") (class "Default")
      (node (ref "C15") (pin "1") (pinfunction "1_1") (pintype "passive"))
      (node (ref "R1") (pin "1") (pinfunction "1_1") (pintype "passive"))
      (node (ref "R3") (pin "2") (pinfunction "2_2") (pintype "passive"))
    )
    (net (code "8") (name "Net-(C16-Pad1)") (class "Default")
      (node (ref "C16") (pin "1") (pinfunction "1_1") (pintype "passive"))
      (node (ref "R2") (pin "1") (pinfunction "1_1") (pintype "passive"))
      (node (ref "R4") (pin "2") (pinfunction "2_2") (pintype "passive"))
    )
    (net (code "9") (name "Net-(C18-Pad1)") (class "Default")
      (node (ref "C18") (pin "1") (pinfunction "1_1") (pintype "passive"))
      (node (ref "R5") (pin "2") (pinfunction "2_2") (pintype "passive"))
      (node (ref "R6") (pin "1") (pinfunction "1_1") (pintype "passive"))
    )
    (net (code "10") (name "Net-(C19-Pad1)") (class "Default")
      (node (ref "C19") (pin "1") (pinfunction "1_1") (pintype "passive"))
      (node (ref "R7") (pin "2") (pinfunction "2_2") (pintype "passive"))
      (node (ref "R8") (pin "1") (pinfunction "1_1") (pintype "passive"))
    )
    (net (code "11") (name "Net-(C21-Pad1)") (class "Default")
      (node (ref "C21") (pin "1") (pinfunction "1_1") (pintype "passive"))
      (node (ref "C22") (pin "2") (pinfunction "2_2") (pintype "passive"))
      (node (ref "R11") (pin "1") (pinfunction "1_1") (pintype "passive"))
    )
    (net (code "12") (name "Net-(C23-Pad1)") (class "Default")
      (node (ref "C23") (pin "1") (pinfunction "1_1") (pintype "passive"))
      (node (ref "C24") (pin "2") (pinfunction "2_2") (pintype "passive"))
      (node (ref "R14") (pin "1") (pinfunction "1_1") (pintype "passive"))
    )
    (net (code "13") (name "Net-(C23-Pad2)") (class "Default")
      (node (ref "C23") (pin "2") (pinfunction "2_2") (pintype "passive"))
      (node (ref "R12") (pin "1") (pinfunction "1_1") (pintype "passive"))
    )
    (net (code "14") (name "Net-(C25-Pad1)") (class "Default")
      (node (ref "C25") (pin "1") (pinfunction "1_1") (pintype "passive"))
      (node (ref "C26") (pin "2") (pinfunction "2_2") (pintype "passive"))
      (node (ref "R18") (pin "1") (pinfunction "1_1") (pintype "passive"))
    )
    (net (code "15") (name "Net-(C25-Pad2)") (class "Default")
      (node (ref "C25") (pin "2") (pinfunction "2_2") (pintype "passive"))
      (node (ref "R21") (pin "1") (pinfunction "1_1") (pintype "passive"))
      (node (ref "R24") (pin "1") (pinfunction "1_1") (pintype "passive"))
    )
    (net (code "16") (name "Net-(C27-Pad1)") (class "Default")
      (node (ref "C27") (pin "1") (pinfunction "1_1") (pintype "passive"))
      (node (ref "C28") (pin "2") (pinfunction "2_2") (pintype "passive"))
      (node (ref "R19") (pin "1") (pinfunction "1_1") (pintype "passive"))
    )
    (net (code "17") (name "Net-(C27-Pad2)") (class "Default")
      (node (ref "C27") (pin "2") (pinfunction "2_2") (pintype "passive"))
      (node (ref "R20") (pin "1") (pinfunction "1_1") (pintype "passive"))
    )
    (net (code "18") (name "Net-(C32-Pad1)") (class "Default")
      (node (ref "C32") (pin "1") (pinfunction "1_1") (pintype "passive"))
      (node (ref "R22") (pin "1") (pinfunction "1_1") (pintype "passive"))
      (node (ref "R27") (pin "2") (pinfunction "2_2") (pintype "passive"))
    )
    (net (code "19") (name "Net-(C33-Pad1)") (class "Default")
      (node (ref "C33") (pin "1") (pinfunction "1_1") (pintype "passive"))
      (node (ref "R28") (pin "1") (pinfunction "1_1") (pintype "passive"))
      (node (ref "R29") (pin "2") (pinfunction "2_2") (pintype "passive"))
    )
    (net (code "20") (name "Net-(C36-Pad1)") (class "Default")
      (node (ref "C36") (pin "1") (pinfunction "1_1") (pintype "passive"))
      (node (ref "R37") (pin "1") (pinfunction "1_1") (pintype "passive"))
      (node (ref "R38") (pin "1") (pinfunction "1_1") (pintype "passive"))
    )
    (net (code "21") (name "Net-(C36-Pad2)") (class "Default")
      (node (ref "C36") (pin "2") (pinfunction "2_2") (pintype "passive"))
      (node (ref "C37") (pin "1") (pinfunction "1_1") (pintype "passive"))
      (node (ref "R39") (pin "2") (pinfunction "2_2") (pintype "passive"))
    )
    (net (code "22") (name "Net-(C37-Pad2)") (class "Default")
      (node (ref "C37") (pin "2") (pinfunction "2_2") (pintype "passive"))
      (node (ref "R1") (pin "2") (pinfunction "2_2") (pintype "passive"))
      (node (ref "R55") (pin "2") (pinfunction "2_2") (pintype "passive"))
    )
    (net (code "23") (name "Net-(C38-Pad1)") (class "Default")
      (node (ref "C38") (pin "1") (pinfunction "1_1") (pintype "passive"))
      (node (ref "C42") (pin "1") (pinfunction "1_1") (pintype "passive"))
      (node (ref "C45") (pin "-") (pinfunction "-_-") (pintype "passive"))
      (node (ref "R36") (pin "2") (pinfunction "2_2") (pintype "passive"))
      (node (ref "R41") (pin "A") (pinfunction "A_A") (pintype "passive"))
      (node (ref "R41") (pin "S") (pinfunction "S_S") (pintype "passive"))
      (node (ref "R43") (pin "2") (pinfunction "2_2") (pintype "passive"))
      (node (ref "R49") (pin "A") (pinfunction "A_A") (pintype "passive"))
      (node (ref "R49") (pin "S") (pinfunction "S_S") (pintype "passive"))
      (node (ref "R53") (pin "2") (pinfunction "2_2") (pintype "passive"))
    )
    (net (code "24") (name "Net-(C39-Pad2)") (class "Default")
      (node (ref "C39") (pin "2") (pinfunction "2_2") (pintype "passive"))
      (node (ref "C44") (pin "+") (pinfunction "+_+") (pintype "passive"))
      (node (ref "Q1") (pin "C") (pinfunction "C_C") (pintype "passive"))
      (node (ref "R42") (pin "2") (pinfunction "2_2") (pintype "passive"))
    )
    (net (code "25") (name "Net-(C40-Pad1)") (class "Default")
      (node (ref "C40") (pin "1") (pinfunction "1_1") (pintype "passive"))
      (node (ref "R45") (pin "1") (pinfunction "1_1") (pintype "passive"))
      (node (ref "R46") (pin "1") (pinfunction "1_1") (pintype "passive"))
    )
    (net (code "26") (name "Net-(C40-Pad2)") (class "Default")
      (node (ref "C40") (pin "2") (pinfunction "2_2") (pintype "passive"))
      (node (ref "C41") (pin "1") (pinfunction "1_1") (pintype "passive"))
      (node (ref "R47") (pin "2") (pinfunction "2_2") (pintype "passive"))
    )
    (net (code "27") (name "Net-(C41-Pad2)") (class "Default")
      (node (ref "C41") (pin "2") (pinfunction "2_2") (pintype "passive"))
      (node (ref "R40") (pin "2") (pinfunction "2_2") (pintype "passive"))
    )
    (net (code "28") (name "Net-(C43-Pad2)") (class "Default")
      (node (ref "C43") (pin "2") (pinfunction "2_2") (pintype "passive"))
      (node (ref "Q3") (pin "C") (pinfunction "C_C") (pintype "passive"))
      (node (ref "R42") (pin "1") (pinfunction "1_1") (pintype "passive"))
      (node (ref "R50") (pin "2") (pinfunction "2_2") (pintype "passive"))
    )
    (net (code "29") (name "Net-(C46-Pad2)") (class "Default")
      (node (ref "C46") (pin "2") (pinfunction "2_2") (pintype "passive"))
      (node (ref "C47") (pin "2") (pinfunction "2_2") (pintype "passive"))
      (node (ref "R48") (pin "2") (pinfunction "2_2") (pintype "passive"))
    )
    (net (code "30") (name "Net-(C48-Pad1)") (class "Default")
      (node (ref "C48") (pin "1") (pinfunction "1_1") (pintype "passive"))
      (node (ref "R58") (pin "1") (pinfunction "1_1") (pintype "passive"))
      (node (ref "R59") (pin "1") (pinfunction "1_1") (pintype "passive"))
    )
    (net (code "31") (name "Net-(C48-Pad2)") (class "Default")
      (node (ref "C48") (pin "2") (pinfunction "2_2") (pintype "passive"))
      (node (ref "C49") (pin "1") (pinfunction "1_1") (pintype "passive"))
      (node (ref "R60") (pin "2") (pinfunction "2_2") (pintype "passive"))
    )
    (net (code "32") (name "Net-(C49-Pad2)") (class "Default")
      (node (ref "C49") (pin "2") (pinfunction "2_2") (pintype "passive"))
      (node (ref "R6") (pin "2") (pinfunction "2_2") (pintype "passive"))
      (node (ref "R74") (pin "2") (pinfunction "2_2") (pintype "passive"))
    )
    (net (code "33") (name "Net-(C50-Pad1)") (class "Default")
      (node (ref "C50") (pin "1") (pinfunction "1_1") (pintype "passive"))
      (node (ref "C54") (pin "1") (pinfunction "1_1") (pintype "passive"))
      (node (ref "C57") (pin "-") (pinfunction "-_-") (pintype "passive"))
      (node (ref "R56") (pin "2") (pinfunction "2_2") (pintype "passive"))
      (node (ref "R62") (pin "A") (pinfunction "A_A") (pintype "passive"))
      (node (ref "R62") (pin "S") (pinfunction "S_S") (pintype "passive"))
      (node (ref "R64") (pin "2") (pinfunction "2_2") (pintype "passive"))
      (node (ref "R70") (pin "A") (pinfunction "A_A") (pintype "passive"))
      (node (ref "R70") (pin "S") (pinfunction "S_S") (pintype "passive"))
      (node (ref "R75") (pin "2") (pinfunction "2_2") (pintype "passive"))
    )
    (net (code "34") (name "Net-(C51-Pad2)") (class "Default")
      (node (ref "C51") (pin "2") (pinfunction "2_2") (pintype "passive"))
      (node (ref "C56") (pin "+") (pinfunction "+_+") (pintype "passive"))
      (node (ref "Q5") (pin "C") (pinfunction "C_C") (pintype "passive"))
      (node (ref "R63") (pin "2") (pinfunction "2_2") (pintype "passive"))
    )
    (net (code "35") (name "Net-(C52-Pad1)") (class "Default")
      (node (ref "C52") (pin "1") (pinfunction "1_1") (pintype "passive"))
      (node (ref "R66") (pin "1") (pinfunction "1_1") (pintype "passive"))
      (node (ref "R67") (pin "1") (pinfunction "1_1") (pintype "passive"))
    )
    (net (code "36") (name "Net-(C52-Pad2)") (class "Default")
      (node (ref "C52") (pin "2") (pinfunction "2_2") (pintype "passive"))
      (node (ref "C53") (pin "1") (pinfunction "1_1") (pintype "passive"))
      (node (ref "R68") (pin "2") (pinfunction "2_2") (pintype "passive"))
    )
    (net (code "37") (name "Net-(C53-Pad2)") (class "Default")
      (node (ref "C53") (pin "2") (pinfunction "2_2") (pintype "passive"))
      (node (ref "R61") (pin "2") (pinfunction "2_2") (pintype "passive"))
    )
    (net (code "38") (name "Net-(C55-Pad2)") (class "Default")
      (node (ref "C55") (pin "2") (pinfunction "2_2") (pintype "passive"))
      (node (ref "Q7") (pin "C") (pinfunction "C_C") (pintype "passive"))
      (node (ref "R63") (pin "1") (pinfunction "1_1") (pintype "passive"))
      (node (ref "R71") (pin "2") (pinfunction "2_2") (pintype "passive"))
    )
    (net (code "39") (name "Net-(C58-Pad2)") (class "Default")
      (node (ref "C58") (pin "2") (pinfunction "2_2") (pintype "passive"))
      (node (ref "C59") (pin "2") (pinfunction "2_2") (pintype "passive"))
      (node (ref "R69") (pin "2") (pinfunction "2_2") (pintype "passive"))
    )
    (net (code "40") (name "Net-(C60-Pad+)") (class "Default")
      (node (ref "C60") (pin "+") (pinfunction "+_+") (pintype "passive"))
      (node (ref "D3") (pin "C") (pinfunction "C_C") (pintype "passive"))
      (node (ref "D5") (pin "A") (pinfunction "A_A") (pintype "passive"))
      (node (ref "Q9") (pin "B") (pinfunction "B_B") (pintype "passive"))
      (node (ref "R81") (pin "2") (pinfunction "2_2") (pintype "passive"))
    )
    (net (code "41") (name "Net-(C61-Pad2)") (class "Default")
      (node (ref "C61") (pin "2") (pinfunction "2_2") (pintype "passive"))
      (node (ref "C62") (pin "+") (pinfunction "+_+") (pintype "passive"))
      (node (ref "IC8") (pin "OUT") (pinfunction "OUT_OUT") (pintype "passive"))
    )
    (net (code "42") (name "Net-(C63-Pad+)") (class "Default")
      (node (ref "C63") (pin "+") (pinfunction "+_+") (pintype "passive"))
      (node (ref "IC8") (pin "IN") (pinfunction "IN_IN") (pintype "input"))
      (node (ref "R50") (pin "1") (pinfunction "1_1") (pintype "passive"))
      (node (ref "R51") (pin "1") (pinfunction "1_1") (pintype "passive"))
      (node (ref "R80") (pin "2") (pinfunction "2_2") (pintype "passive"))
      (node (ref "R82") (pin "2") (pinfunction "2_2") (pintype "passive"))
      (node (ref "R83") (pin "2") (pinfunction "2_2") (pintype "passive"))
    )
    (net (code "43") (name "Net-(D2-PadA)") (class "Default")
      (node (ref "D2") (pin "A") (pinfunction "A_A") (pintype "passive"))
      (node (ref "K1") (pin "1") (pinfunction "1_1") (pintype "passive"))
      (node (ref "Q9") (pin "C") (pinfunction "C_C") (pintype "passive"))
      (node (ref "R85") (pin "1") (pinfunction "1_1") (pintype "passive"))
    )
    (net (code "44") (name "Net-(D5-PadC)") (class "Default")
      (node (ref "D5") (pin "C") (pinfunction "C_C") (pintype "passive"))
      (node (ref "Q10") (pin "C") (pinfunction "C_C") (pintype "passive"))
      (node (ref "R81") (pin "1") (pinfunction "1_1") (pintype "passive"))
      (node (ref "R82") (pin "1") (pinfunction "1_1") (pintype "passive"))
    )
    (net (code "45") (name "Net-(IC1A-+IN)") (class "Default")
      (node (ref "C13") (pin "2") (pinfunction "2_2") (pintype "passive"))
      (node (ref "IC1") (pin "3") (pinfunction "+IN_3") (pintype "input"))
      (node (ref "R3") (pin "1") (pinfunction "1_1") (pintype "passive"))
    )
    (net (code "46") (name "Net-(IC1A--IN)") (class "Default")
      (node (ref "C15") (pin "2") (pinfunction "2_2") (pintype "passive"))
      (node (ref "IC1") (pin "1") (pinfunction "OUT_1") (pintype "output"))
      (node (ref "IC1") (pin "2") (pinfunction "-IN_2") (pintype "input"))
      (node (ref "R2") (pin "2") (pinfunction "2_2") (pintype "passive"))
    )
    (net (code "47") (name "Net-(IC1B-+IN)") (class "Default")
      (node (ref "C14") (pin "2") (pinfunction "2_2") (pintype "passive"))
      (node (ref "IC1") (pin "5") (pinfunction "+IN_5") (pintype "input"))
      (node (ref "R4") (pin "1") (pinfunction "1_1") (pintype "passive"))
    )
    (net (code "48") (name "Net-(IC1B--IN)") (class "Default")
      (node (ref "C16") (pin "2") (pinfunction "2_2") (pintype "passive"))
      (node (ref "C21") (pin "2") (pinfunction "2_2") (pintype "passive"))
      (node (ref "IC1") (pin "6") (pinfunction "-IN_6") (pintype "input"))
      (node (ref "IC1") (pin "7") (pinfunction "OUT_7") (pintype "output"))
      (node (ref "R9") (pin "2") (pinfunction "2_2") (pintype "passive"))
    )
    (net (code "49") (name "Net-(IC2A-+IN)") (class "Default")
      (node (ref "C24") (pin "1") (pinfunction "1_1") (pintype "passive"))
      (node (ref "IC2") (pin "3") (pinfunction "+IN_3") (pintype "input"))
      (node (ref "R13") (pin "1") (pinfunction "1_1") (pintype "passive"))
    )
    (net (code "50") (name "Net-(IC2A--IN)") (class "Default")
      (node (ref "IC2") (pin "1") (pinfunction "OUT_1") (pintype "output"))
      (node (ref "IC2") (pin "2") (pinfunction "-IN_2") (pintype "input"))
      (node (ref "R14") (pin "2") (pinfunction "2_2") (pintype "passive"))
      (node (ref "R30") (pin "1") (pinfunction "1_1") (pintype "passive"))
    )
    (net (code "51") (name "Net-(IC2B-+IN)") (class "Default")
      (node (ref "C22") (pin "1") (pinfunction "1_1") (pintype "passive"))
      (node (ref "IC2") (pin "5") (pinfunction "+IN_5") (pintype "input"))
      (node (ref "R10") (pin "1") (pinfunction "1_1") (pintype "passive"))
    )
    (net (code "52") (name "Net-(IC2B--IN)") (class "Default")
      (node (ref "IC2") (pin "6") (pinfunction "-IN_6") (pintype "input"))
      (node (ref "IC2") (pin "7") (pinfunction "OUT_7") (pintype "output"))
      (node (ref "R11") (pin "2") (pinfunction "2_2") (pintype "passive"))
      (node (ref "R12") (pin "2") (pinfunction "2_2") (pintype "passive"))
    )
    (net (code "53") (name "Net-(IC3A-+IN)") (class "Default")
      (node (ref "C31") (pin "1") (pinfunction "1_1") (pintype "passive"))
      (node (ref "IC3") (pin "3") (pinfunction "+IN_3") (pintype "input"))
      (node (ref "R28") (pin "2") (pinfunction "2_2") (pintype "passive"))
    )
    (net (code "54") (name "Net-(IC3A--IN)") (class "Default")
      (node (ref "C33") (pin "2") (pinfunction "2_2") (pintype "passive"))
      (node (ref "IC3") (pin "1") (pinfunction "OUT_1") (pintype "output"))
      (node (ref "IC3") (pin "2") (pinfunction "-IN_2") (pintype "input"))
      (node (ref "R32") (pin "1") (pinfunction "1_1") (pintype "passive"))
    )
    (net (code "55") (name "Net-(IC3B-+IN)") (class "Default")
      (node (ref "C30") (pin "1") (pinfunction "1_1") (pintype "passive"))
      (node (ref "IC3") (pin "5") (pinfunction "+IN_5") (pintype "input"))
      (node (ref "R22") (pin "2") (pinfunction "2_2") (pintype "passive"))
    )
    (net (code "56") (name "Net-(IC3B--IN)") (class "Default")
      (node (ref "C32") (pin "2") (pinfunction "2_2") (pintype "passive"))
      (node (ref "IC3") (pin "6") (pinfunction "-IN_6") (pintype "input"))
      (node (ref "IC3") (pin "7") (pinfunction "OUT_7") (pintype "output"))
      (node (ref "R29") (pin "1") (pinfunction "1_1") (pintype "passive"))
    )
    (net (code "57") (name "Net-(IC4A-+IN)") (class "Default")
      (node (ref "C26") (pin "1") (pinfunction "1_1") (pintype "passive"))
      (node (ref "IC4") (pin "3") (pinfunction "+IN_3") (pintype "input"))
      (node (ref "R16") (pin "1") (pinfunction "1_1") (pintype "passive"))
    )
    (net (code "58") (name "Net-(IC4A--IN)") (class "Default")
      (node (ref "IC4") (pin "1") (pinfunction "OUT_1") (pintype "output"))
      (node (ref "IC4") (pin "2") (pinfunction "-IN_2") (pintype "input"))
      (node (ref "R18") (pin "2") (pinfunction "2_2") (pintype "passive"))
      (node (ref "R20") (pin "2") (pinfunction "2_2") (pintype "passive"))
    )
    (net (code "59") (name "Net-(IC4B-+IN)") (class "Default")
      (node (ref "C28") (pin "1") (pinfunction "1_1") (pintype "passive"))
      (node (ref "IC4") (pin "5") (pinfunction "+IN_5") (pintype "input"))
      (node (ref "R17") (pin "1") (pinfunction "1_1") (pintype "passive"))
    )
    (net (code "60") (name "Net-(IC4B--IN)") (class "Default")
      (node (ref "IC4") (pin "6") (pinfunction "-IN_6") (pintype "input"))
      (node (ref "IC4") (pin "7") (pinfunction "OUT_7") (pintype "output"))
      (node (ref "R19") (pin "2") (pinfunction "2_2") (pintype "passive"))
      (node (ref "R31") (pin "1") (pinfunction "1_1") (pintype "passive"))
    )
    (net (code "61") (name "Net-(IC5A-+IN)") (class "Default")
      (node (ref "C20") (pin "2") (pinfunction "2_2") (pintype "passive"))
      (node (ref "IC5") (pin "3") (pinfunction "+IN_3") (pintype "input"))
      (node (ref "R7") (pin "1") (pinfunction "1_1") (pintype "passive"))
    )
    (net (code "62") (name "Net-(IC5A--IN)") (class "Default")
      (node (ref "C19") (pin "2") (pinfunction "2_2") (pintype "passive"))
      (node (ref "IC5") (pin "1") (pinfunction "OUT_1") (pintype "output"))
      (node (ref "IC5") (pin "2") (pinfunction "-IN_2") (pintype "input"))
      (node (ref "R21") (pin "2") (pinfunction "2_2") (pintype "passive"))
    )
    (net (code "63") (name "Net-(IC5B-+IN)") (class "Default")
      (node (ref "C17") (pin "2") (pinfunction "2_2") (pintype "passive"))
      (node (ref "IC5") (pin "5") (pinfunction "+IN_5") (pintype "input"))
      (node (ref "R5") (pin "1") (pinfunction "1_1") (pintype "passive"))
    )
    (net (code "64") (name "Net-(IC5B--IN)") (class "Default")
      (node (ref "C18") (pin "2") (pinfunction "2_2") (pintype "passive"))
      (node (ref "IC5") (pin "6") (pinfunction "-IN_6") (pintype "input"))
      (node (ref "IC5") (pin "7") (pinfunction "OUT_7") (pintype "output"))
      (node (ref "R8") (pin "2") (pinfunction "2_2") (pintype "passive"))
    )
    (net (code "65") (name "Net-(IC6-+IN)") (class "Default")
      (node (ref "IC6") (pin "3") (pinfunction "+IN_3") (pintype "input"))
      (node (ref "R23") (pin "1") (pinfunction "1_1") (pintype "passive"))
    )
    (net (code "66") (name "Net-(IC6--IN)") (class "Default")
      (node (ref "IC6") (pin "2") (pinfunction "-IN_2") (pintype "input"))
      (node (ref "R24") (pin "2") (pinfunction "2_2") (pintype "passive"))
      (node (ref "R25") (pin "2") (pinfunction "2_2") (pintype "passive"))
      (node (ref "R26") (pin "1") (pinfunction "1_1") (pintype "passive"))
    )
    (net (code "67") (name "Net-(IC6-OUT)") (class "Default")
      (node (ref "IC6") (pin "6") (pinfunction "OUT_6") (pintype "output"))
      (node (ref "R26") (pin "2") (pinfunction "2_2") (pintype "passive"))
      (node (ref "R27") (pin "1") (pinfunction "1_1") (pintype "passive"))
    )
    (net (code "68") (name "Net-(K1A-2)") (class "Default")
      (node (ref "D2") (pin "C") (pinfunction "C_C") (pintype "passive"))
      (node (ref "K1") (pin "16") (pinfunction "2_16") (pintype "passive"))
      (node (ref "R80") (pin "1") (pinfunction "1_1") (pintype "passive"))
    )
    (net (code "69") (name "Net-(K1B-O)") (class "Default")
      (node (ref "K1") (pin "O1") (pinfunction "O_O1") (pintype "passive"))
      (node (ref "R79") (pin "1") (pinfunction "1_1") (pintype "passive"))
    )
    (net (code "70") (name "Net-(K1C-O)") (class "Default")
      (node (ref "K1") (pin "O2") (pinfunction "O_O2") (pintype "passive"))
      (node (ref "R78") (pin "2") (pinfunction "2_2") (pintype "passive"))
    )
    (net (code "71") (name "Net-(OK1-A)") (class "Default")
      (node (ref "D1") (pin "C") (pinfunction "C_C") (pintype "passive"))
      (node (ref "OK1") (pin "1") (pinfunction "A_1") (pintype "passive"))
      (node (ref "X4") (pin "1") (pinfunction "S_1") (pintype "passive"))
    )
    (net (code "72") (name "Net-(OK1-C)") (class "Default")
      (node (ref "D1") (pin "A") (pinfunction "A_A") (pintype "passive"))
      (node (ref "OK1") (pin "2") (pinfunction "C_2") (pintype "passive"))
      (node (ref "X4") (pin "2") (pinfunction "S_2") (pintype "passive"))
    )
    (net (code "73") (name "Net-(OK1-COL)") (class "Default")
      (node (ref "OK1") (pin "5") (pinfunction "COL_5") (pintype "passive"))
      (node (ref "R84") (pin "2") (pinfunction "2_2") (pintype "passive"))
    )
    (net (code "74") (name "Net-(Q1-PadB)") (class "Default")
      (node (ref "Q1") (pin "B") (pinfunction "B_B") (pintype "passive"))
      (node (ref "R37") (pin "2") (pinfunction "2_2") (pintype "passive"))
    )
    (net (code "75") (name "Net-(Q1-PadE)") (class "Default")
      (node (ref "Q1") (pin "E") (pinfunction "E_E") (pintype "passive"))
      (node (ref "R35") (pin "1") (pinfunction "1_1") (pintype "passive"))
    )
    (net (code "76") (name "Net-(Q2-PadB)") (class "Default")
      (node (ref "Q2") (pin "B") (pinfunction "B_B") (pintype "passive"))
      (node (ref "R41") (pin "E") (pinfunction "E_E") (pintype "passive"))
    )
    (net (code "77") (name "Net-(Q2-PadC)") (class "Default")
      (node (ref "Q2") (pin "C") (pinfunction "C_C") (pintype "passive"))
      (node (ref "R35") (pin "2") (pinfunction "2_2") (pintype "passive"))
      (node (ref "R39") (pin "1") (pinfunction "1_1") (pintype "passive"))
      (node (ref "R40") (pin "1") (pinfunction "1_1") (pintype "passive"))
    )
    (net (code "78") (name "Net-(Q2-PadE)") (class "Default")
      (node (ref "Q2") (pin "E") (pinfunction "E_E") (pintype "passive"))
      (node (ref "R36") (pin "1") (pinfunction "1_1") (pintype "passive"))
    )
    (net (code "79") (name "Net-(Q3-PadB)") (class "Default")
      (node (ref "Q3") (pin "B") (pinfunction "B_B") (pintype "passive"))
      (node (ref "R45") (pin "2") (pinfunction "2_2") (pintype "passive"))
    )
    (net (code "80") (name "Net-(Q3-PadE)") (class "Default")
      (node (ref "Q3") (pin "E") (pinfunction "E_E") (pintype "passive"))
      (node (ref "R44") (pin "1") (pinfunction "1_1") (pintype "passive"))
    )
    (net (code "81") (name "Net-(Q4-PadB)") (class "Default")
      (node (ref "Q4") (pin "B") (pinfunction "B_B") (pintype "passive"))
      (node (ref "R49") (pin "E") (pinfunction "E_E") (pintype "passive"))
    )
    (net (code "82") (name "Net-(Q4-PadC)") (class "Default")
      (node (ref "Q4") (pin "C") (pinfunction "C_C") (pintype "passive"))
      (node (ref "R44") (pin "2") (pinfunction "2_2") (pintype "passive"))
      (node (ref "R47") (pin "1") (pinfunction "1_1") (pintype "passive"))
      (node (ref "R48") (pin "1") (pinfunction "1_1") (pintype "passive"))
    )
    (net (code "83") (name "Net-(Q4-PadE)") (class "Default")
      (node (ref "Q4") (pin "E") (pinfunction "E_E") (pintype "passive"))
      (node (ref "R43") (pin "1") (pinfunction "1_1") (pintype "passive"))
    )
    (net (code "84") (name "Net-(Q5-PadB)") (class "Default")
      (node (ref "Q5") (pin "B") (pinfunction "B_B") (pintype "passive"))
      (node (ref "R58") (pin "2") (pinfunction "2_2") (pintype "passive"))
    )
    (net (code "85") (name "Net-(Q5-PadE)") (class "Default")
      (node (ref "Q5") (pin "E") (pinfunction "E_E") (pintype "passive"))
      (node (ref "R57") (pin "1") (pinfunction "1_1") (pintype "passive"))
    )
    (net (code "86") (name "Net-(Q6-PadB)") (class "Default")
      (node (ref "Q6") (pin "B") (pinfunction "B_B") (pintype "passive"))
      (node (ref "R62") (pin "E") (pinfunction "E_E") (pintype "passive"))
    )
    (net (code "87") (name "Net-(Q6-PadC)") (class "Default")
      (node (ref "Q6") (pin "C") (pinfunction "C_C") (pintype "passive"))
      (node (ref "R57") (pin "2") (pinfunction "2_2") (pintype "passive"))
      (node (ref "R60") (pin "1") (pinfunction "1_1") (pintype "passive"))
      (node (ref "R61") (pin "1") (pinfunction "1_1") (pintype "passive"))
    )
    (net (code "88") (name "Net-(Q6-PadE)") (class "Default")
      (node (ref "Q6") (pin "E") (pinfunction "E_E") (pintype "passive"))
      (node (ref "R56") (pin "1") (pinfunction "1_1") (pintype "passive"))
    )
    (net (code "89") (name "Net-(Q7-PadB)") (class "Default")
      (node (ref "Q7") (pin "B") (pinfunction "B_B") (pintype "passive"))
      (node (ref "R66") (pin "2") (pinfunction "2_2") (pintype "passive"))
    )
    (net (code "90") (name "Net-(Q7-PadE)") (class "Default")
      (node (ref "Q7") (pin "E") (pinfunction "E_E") (pintype "passive"))
      (node (ref "R65") (pin "1") (pinfunction "1_1") (pintype "passive"))
    )
    (net (code "91") (name "Net-(Q8-PadB)") (class "Default")
      (node (ref "Q8") (pin "B") (pinfunction "B_B") (pintype "passive"))
      (node (ref "R70") (pin "E") (pinfunction "E_E") (pintype "passive"))
    )
    (net (code "92") (name "Net-(Q8-PadC)") (class "Default")
      (node (ref "Q8") (pin "C") (pinfunction "C_C") (pintype "passive"))
      (node (ref "R65") (pin "2") (pinfunction "2_2") (pintype "passive"))
      (node (ref "R68") (pin "1") (pinfunction "1_1") (pintype "passive"))
      (node (ref "R69") (pin "1") (pinfunction "1_1") (pintype "passive"))
    )
    (net (code "93") (name "Net-(Q8-PadE)") (class "Default")
      (node (ref "Q8") (pin "E") (pinfunction "E_E") (pintype "passive"))
      (node (ref "R64") (pin "1") (pinfunction "1_1") (pintype "passive"))
    )
    (net (code "94") (name "Net-(Q10-PadB)") (class "Default")
      (node (ref "Q10") (pin "B") (pinfunction "B_B") (pintype "passive"))
      (node (ref "R83") (pin "1") (pinfunction "1_1") (pintype "passive"))
      (node (ref "R84") (pin "1") (pinfunction "1_1") (pintype "passive"))
    )
    (net (code "95") (name "Net-(R15-Pad1)") (class "Default")
      (node (ref "R15") (pin "1") (pinfunction "1_1") (pintype "passive"))
      (node (ref "R25") (pin "1") (pinfunction "1_1") (pintype "passive"))
    )
    (net (code "96") (name "Net-(R15-Pad2)") (class "Default")
      (node (ref "R15") (pin "2") (pinfunction "2_2") (pintype "passive"))
      (node (ref "R9") (pin "1") (pinfunction "1_1") (pintype "passive"))
    )
    (net (code "97") (name "Net-(R30-Pad2)") (class "Default")
      (node (ref "R30") (pin "2") (pinfunction "2_2") (pintype "passive"))
      (node (ref "R33") (pin "1") (pinfunction "1_1") (pintype "passive"))
    )
    (net (code "98") (name "Net-(R31-Pad2)") (class "Default")
      (node (ref "R31") (pin "2") (pinfunction "2_2") (pintype "passive"))
      (node (ref "R34") (pin "1") (pinfunction "1_1") (pintype "passive"))
    )
    (net (code "99") (name "Net-(R52-Pad2)") (class "Default")
      (node (ref "R52") (pin "2") (pinfunction "2_2") (pintype "passive"))
      (node (ref "R53") (pin "1") (pinfunction "1_1") (pintype "passive"))
    )
    (net (code "100") (name "Net-(R72-Pad2)") (class "Default")
      (node (ref "R72") (pin "2") (pinfunction "2_2") (pintype "passive"))
      (node (ref "R75") (pin "1") (pinfunction "1_1") (pintype "passive"))
    )
    (net (code "101") (name "Net-(R85-Pad2)") (class "Default")
      (node (ref "R85") (pin "2") (pinfunction "2_2") (pintype "passive"))
      (node (ref "R86") (pin "1") (pinfunction "1_1") (pintype "passive"))
    )
    (net (code "102") (name "Net-(X1A-S)") (class "Default")
      (node (ref "R34") (pin "2") (pinfunction "2_2") (pintype "passive"))
      (node (ref "X1") (pin "1") (pinfunction "S_1") (pintype "passive"))
    )
    (net (code "103") (name "Net-(X1C-S)") (class "Default")
      (node (ref "R32") (pin "2") (pinfunction "2_2") (pintype "passive"))
      (node (ref "X1") (pin "3") (pinfunction "S_3") (pintype "passive"))
    )
    (net (code "104") (name "Net-(X1E-S)") (class "Default")
      (node (ref "R33") (pin "2") (pinfunction "2_2") (pintype "passive"))
      (node (ref "X1") (pin "5") (pinfunction "S_5") (pintype "passive"))
    )
    (net (code "105") (name "Net-(X2A-S)") (class "Default")
      (node (ref "R55") (pin "1") (pinfunction "1_1") (pintype "passive"))
      (node (ref "X2") (pin "1") (pinfunction "S_1") (pintype "passive"))
    )
    (net (code "106") (name "Net-(X2C-S)") (class "Default")
      (node (ref "C46") (pin "1") (pinfunction "1_1") (pintype "passive"))
      (node (ref "C47") (pin "1") (pinfunction "1_1") (pintype "passive"))
      (node (ref "R54") (pin "1") (pinfunction "1_1") (pintype "passive"))
      (node (ref "R79") (pin "2") (pinfunction "2_2") (pintype "passive"))
      (node (ref "X2") (pin "3") (pinfunction "S_3") (pintype "passive"))
    )
    (net (code "107") (name "Net-(X3A-S)") (class "Default")
      (node (ref "R74") (pin "1") (pinfunction "1_1") (pintype "passive"))
      (node (ref "X3") (pin "1") (pinfunction "S_1") (pintype "passive"))
    )
    (net (code "108") (name "Net-(X3C-S)") (class "Default")
      (node (ref "C58") (pin "1") (pinfunction "1_1") (pintype "passive"))
      (node (ref "C59") (pin "1") (pinfunction "1_1") (pintype "passive"))
      (node (ref "R73") (pin "1") (pinfunction "1_1") (pintype "passive"))
      (node (ref "R78") (pin "1") (pinfunction "1_1") (pintype "passive"))
      (node (ref "X3") (pin "3") (pinfunction "S_3") (pintype "passive"))
    )
    (net (code "109") (name "Net-(X4C-S)") (class "Default")
      (node (ref "C61") (pin "1") (pinfunction "1_1") (pintype "passive"))
      (node (ref "D4") (pin "C") (pinfunction "C_C") (pintype "passive"))
      (node (ref "X4") (pin "3") (pinfunction "S_3") (pintype "passive"))
    )
    (net (code "110") (name "unconnected-(IC6-ON1-Pad1)") (class "Default")
      (node (ref "IC6") (pin "1") (pinfunction "ON1_1") (pintype "passive"))
    )
    (net (code "111") (name "unconnected-(IC6-ON2-Pad8)") (class "Default")
      (node (ref "IC6") (pin "8") (pinfunction "ON2_8") (pintype "passive"))
    )
    (net (code "112") (name "unconnected-(IC6-OPT-Pad5)") (class "Default")
      (node (ref "IC6") (pin "5") (pinfunction "OPT_5") (pintype "passive"))
    )
    (net (code "113") (name "unconnected-(OK1-BAS-Pad6)") (class "Default")
      (node (ref "OK1") (pin "6") (pinfunction "BAS_6") (pintype "passive"))
    )
  )
)
